# IPMC_V71V01.net
KiCad netlist of a schematic drawn in Altium Designer
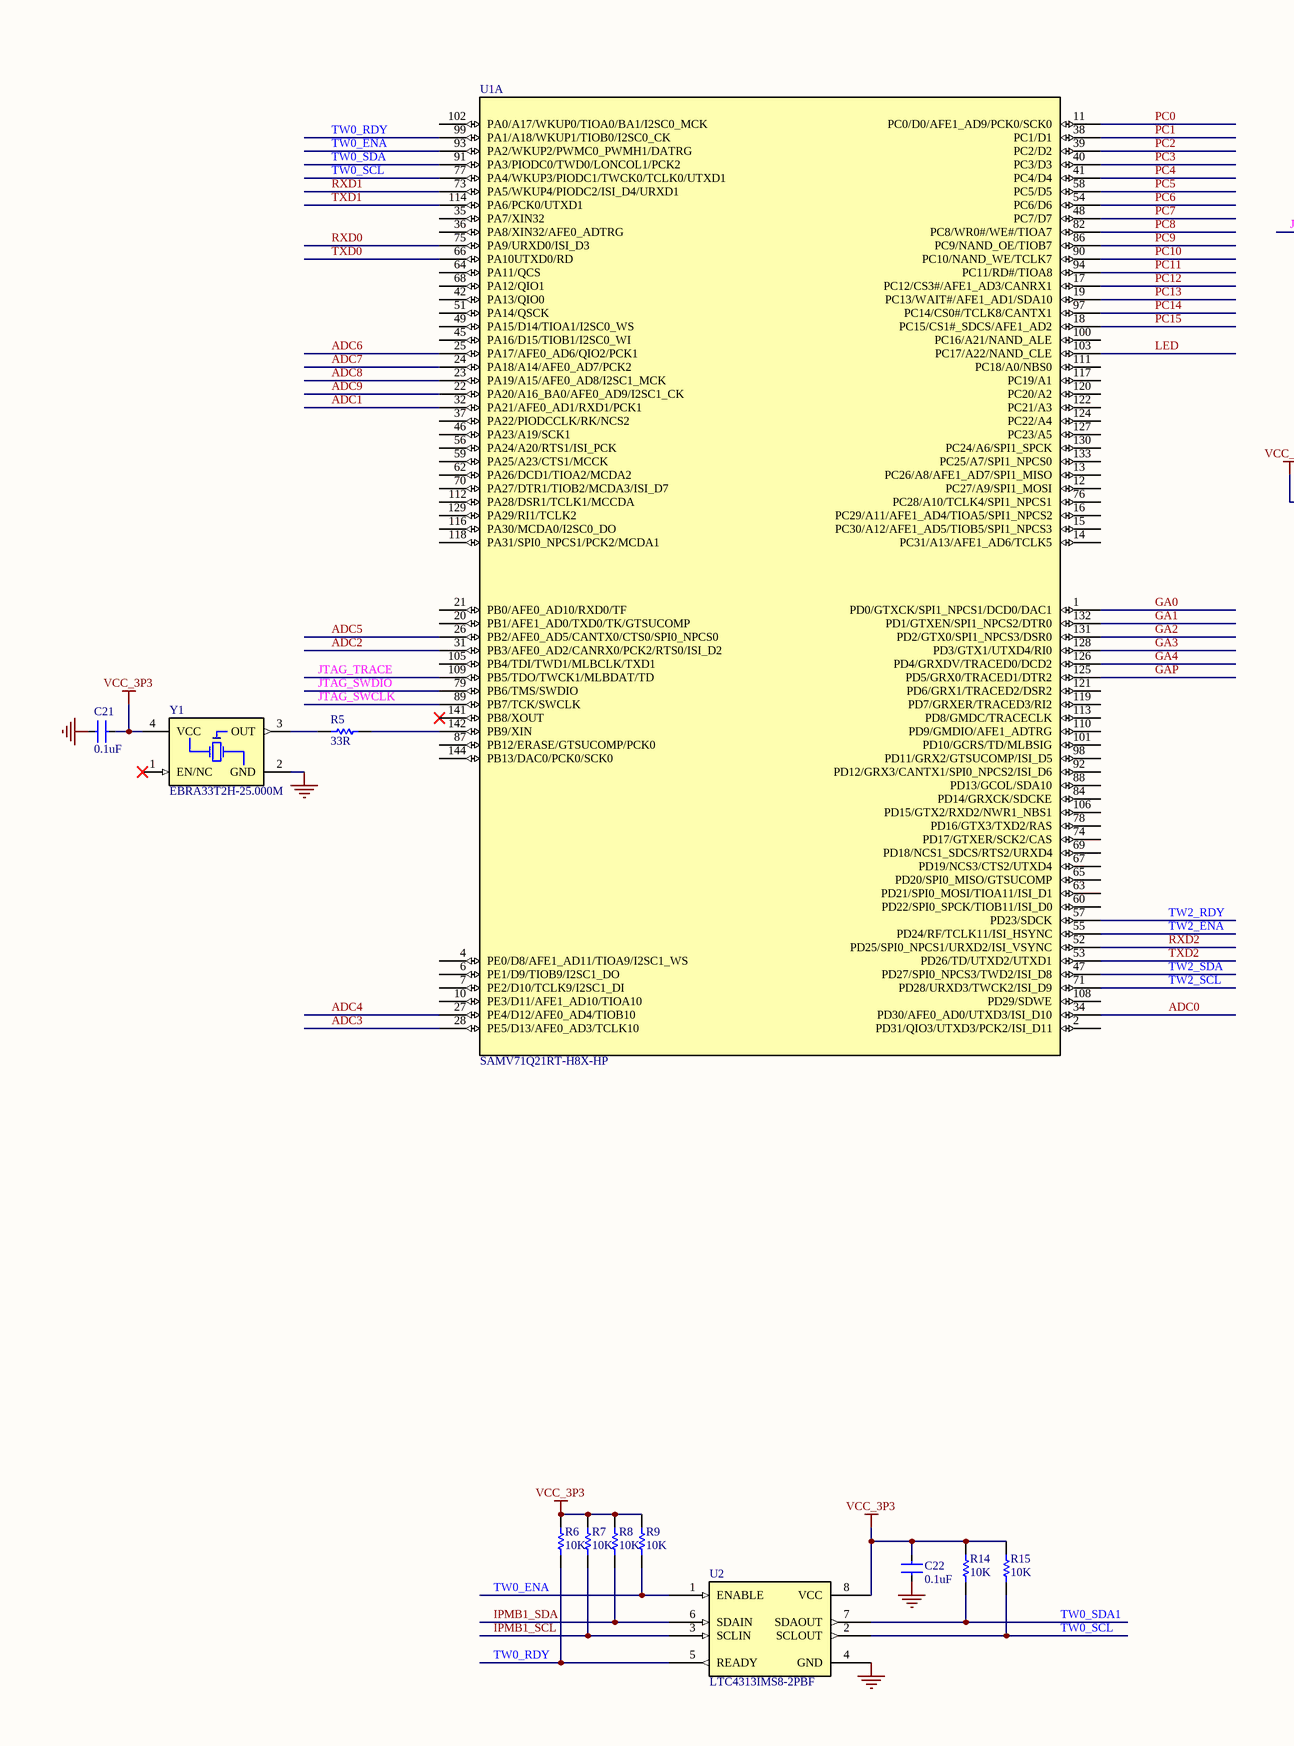
[diagram p0: IPMC_V71V01.SchDoc, left]
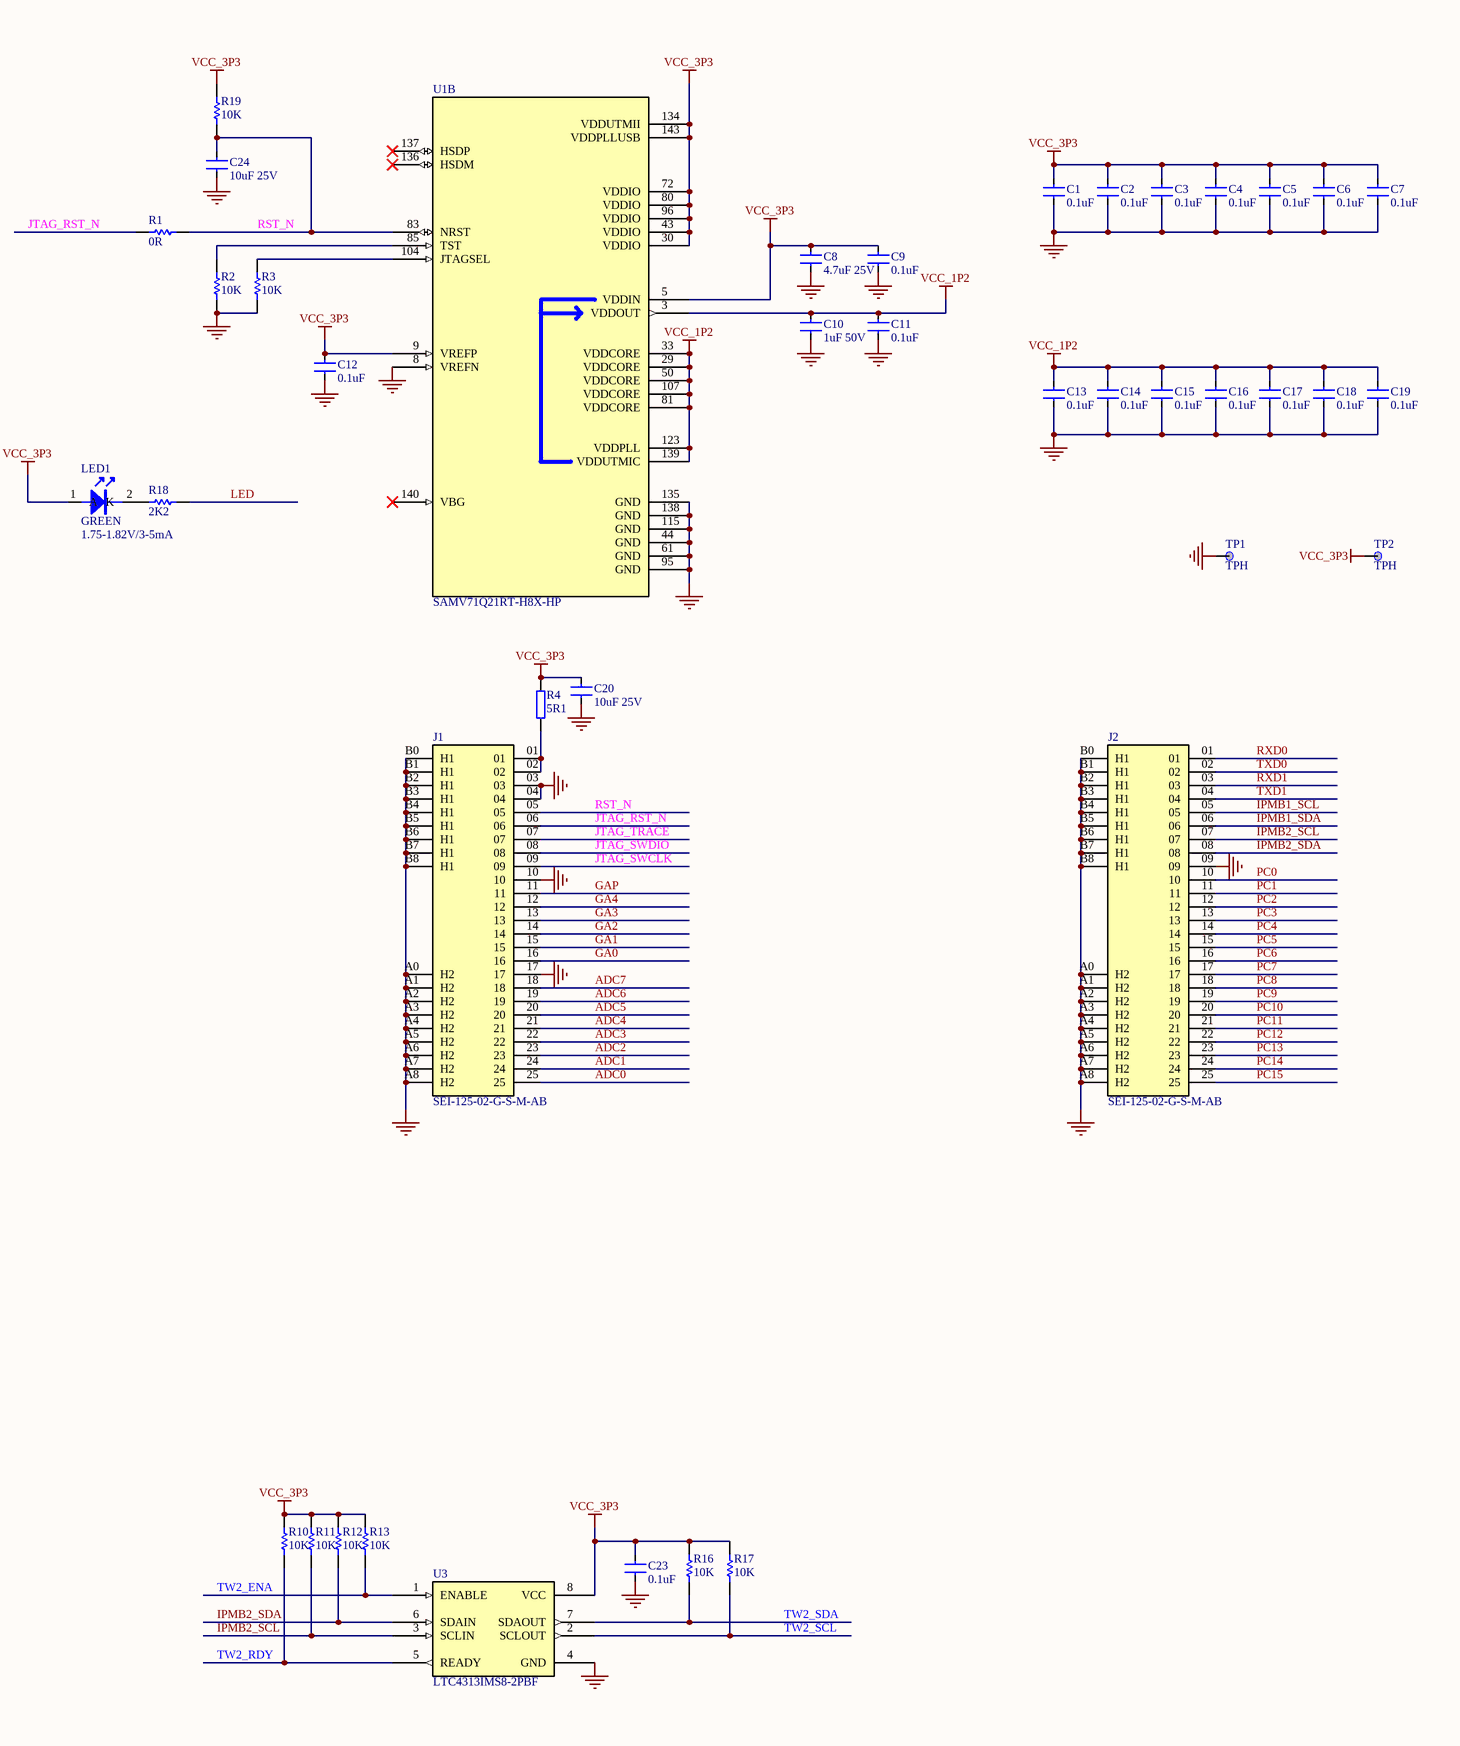
[diagram p1: IPMC_V71V01.SchDoc, right]

(export (version "E")
  (design (tool "Eeschema 10.0.6"))
  (components
    (comp (ref "C1")
      (value "0.1uF")
      (footprint "0603C")
      (description "X8L AEC-Q200")
      (fields (field (name "MANUFACTURER") "muRata") (field (name "PARTNUMBER") "GCJ188L8EL104KA07"))
      (libsource (lib "AD20_RCX") (part "CAP-0.1u-100v-0603"))
    )
    (comp (ref "C2")
      (value "0.1uF")
      (footprint "0603C")
      (description "X8L AEC-Q200")
      (fields (field (name "MANUFACTURER") "muRata") (field (name "PARTNUMBER") "GCJ188L8EL104KA07"))
      (libsource (lib "AD20_RCX") (part "CAP-0.1u-100v-0603"))
    )
    (comp (ref "C3")
      (value "0.1uF")
      (footprint "0603C")
      (description "X8L AEC-Q200")
      (fields (field (name "MANUFACTURER") "muRata") (field (name "PARTNUMBER") "GCJ188L8EL104KA07"))
      (libsource (lib "AD20_RCX") (part "CAP-0.1u-100v-0603"))
    )
    (comp (ref "C4")
      (value "0.1uF")
      (footprint "0603C")
      (description "X8L AEC-Q200")
      (fields (field (name "MANUFACTURER") "muRata") (field (name "PARTNUMBER") "GCJ188L8EL104KA07"))
      (libsource (lib "AD20_RCX") (part "CAP-0.1u-100v-0603"))
    )
    (comp (ref "C5")
      (value "0.1uF")
      (footprint "0603C")
      (description "X8L AEC-Q200")
      (fields (field (name "MANUFACTURER") "muRata") (field (name "PARTNUMBER") "GCJ188L8EL104KA07"))
      (libsource (lib "AD20_RCX") (part "CAP-0.1u-100v-0603"))
    )
    (comp (ref "C6")
      (value "0.1uF")
      (footprint "0603C")
      (description "X8L AEC-Q200")
      (fields (field (name "MANUFACTURER") "muRata") (field (name "PARTNUMBER") "GCJ188L8EL104KA07"))
      (libsource (lib "AD20_RCX") (part "CAP-0.1u-100v-0603"))
    )
    (comp (ref "C7")
      (value "0.1uF")
      (footprint "0603C")
      (description "X8L AEC-Q200")
      (fields (field (name "MANUFACTURER") "muRata") (field (name "PARTNUMBER") "GCJ188L8EL104KA07"))
      (libsource (lib "AD20_RCX") (part "CAP-0.1u-100v-0603"))
    )
    (comp (ref "C8")
      (value "4.7uF 25V")
      (footprint "0603C")
      (description "X5R AEC-Q200")
      (fields (field (name "PARTNUMBER") "GRT188R61E475KE13") (field (name "MANUFACTURER") "muRata"))
      (libsource (lib "AD20_RCX") (part "CAP-4.7u-25v-0603"))
    )
    (comp (ref "C9")
      (value "0.1uF")
      (footprint "0603C")
      (description "X8L AEC-Q200")
      (fields (field (name "MANUFACTURER") "muRata") (field (name "PARTNUMBER") "GCJ188L8EL104KA07"))
      (libsource (lib "AD20_RCX") (part "CAP-0.1u-100v-0603"))
    )
    (comp (ref "C10")
      (value "1uF 50V")
      (footprint "0603C")
      (description "X5R AEC-Q200")
      (fields (field (name "PARTNUMBER") "GRT188R61H105KE13") (field (name "MANUFACTURER") "muRata"))
      (libsource (lib "AD20_RCX") (part "CAP-1u-50v-0603"))
    )
    (comp (ref "C11")
      (value "0.1uF")
      (footprint "0603C")
      (description "X8L AEC-Q200")
      (fields (field (name "MANUFACTURER") "muRata") (field (name "PARTNUMBER") "GCJ188L8EL104KA07"))
      (libsource (lib "AD20_RCX") (part "CAP-0.1u-100v-0603"))
    )
    (comp (ref "C12")
      (value "0.1uF")
      (footprint "0603C")
      (description "X8L AEC-Q200")
      (fields (field (name "MANUFACTURER") "muRata") (field (name "PARTNUMBER") "GCJ188L8EL104KA07"))
      (libsource (lib "AD20_RCX") (part "CAP-0.1u-100v-0603"))
    )
    (comp (ref "C13")
      (value "0.1uF")
      (footprint "0603C")
      (description "X8L AEC-Q200")
      (fields (field (name "MANUFACTURER") "muRata") (field (name "PARTNUMBER") "GCJ188L8EL104KA07"))
      (libsource (lib "AD20_RCX") (part "CAP-0.1u-100v-0603"))
    )
    (comp (ref "C14")
      (value "0.1uF")
      (footprint "0603C")
      (description "X8L AEC-Q200")
      (fields (field (name "MANUFACTURER") "muRata") (field (name "PARTNUMBER") "GCJ188L8EL104KA07"))
      (libsource (lib "AD20_RCX") (part "CAP-0.1u-100v-0603"))
    )
    (comp (ref "C15")
      (value "0.1uF")
      (footprint "0603C")
      (description "X8L AEC-Q200")
      (fields (field (name "MANUFACTURER") "muRata") (field (name "PARTNUMBER") "GCJ188L8EL104KA07"))
      (libsource (lib "AD20_RCX") (part "CAP-0.1u-100v-0603"))
    )
    (comp (ref "C16")
      (value "0.1uF")
      (footprint "0603C")
      (description "X8L AEC-Q200")
      (fields (field (name "MANUFACTURER") "muRata") (field (name "PARTNUMBER") "GCJ188L8EL104KA07"))
      (libsource (lib "AD20_RCX") (part "CAP-0.1u-100v-0603"))
    )
    (comp (ref "C17")
      (value "0.1uF")
      (footprint "0603C")
      (description "X8L AEC-Q200")
      (fields (field (name "MANUFACTURER") "muRata") (field (name "PARTNUMBER") "GCJ188L8EL104KA07"))
      (libsource (lib "AD20_RCX") (part "CAP-0.1u-100v-0603"))
    )
    (comp (ref "C18")
      (value "0.1uF")
      (footprint "0603C")
      (description "X8L AEC-Q200")
      (fields (field (name "MANUFACTURER") "muRata") (field (name "PARTNUMBER") "GCJ188L8EL104KA07"))
      (libsource (lib "AD20_RCX") (part "CAP-0.1u-100v-0603"))
    )
    (comp (ref "C19")
      (value "0.1uF")
      (footprint "0603C")
      (description "X8L AEC-Q200")
      (fields (field (name "MANUFACTURER") "muRata") (field (name "PARTNUMBER") "GCJ188L8EL104KA07"))
      (libsource (lib "AD20_RCX") (part "CAP-0.1u-100v-0603"))
    )
    (comp (ref "C20")
      (value "10uF 25V")
      (footprint "0603C")
      (description "X5R AEC-Q200")
      (fields (field (name "PARTNUMBER") "GRT188R61E106ME13") (field (name "MANUFACTURER") "muRata"))
      (libsource (lib "AD20_RCX") (part "CAP-10u-25v-0603"))
    )
    (comp (ref "C21")
      (value "0.1uF")
      (footprint "0603C")
      (description "X7R AEC-Q200")
      (fields (field (name "PARTNUMBER") "GCJ188R71H104KA12") (field (name "MANUFACTURER") "muRata"))
      (libsource (lib "AD") (part "CAP-0.1u-50v-0603"))
    )
    (comp (ref "C22")
      (value "0.1uF")
      (footprint "0603C")
      (description "X7R AEC-Q200")
      (fields (field (name "PARTNUMBER") "GCJ188R71H104KA12") (field (name "MANUFACTURER") "muRata"))
      (libsource (lib "AD") (part "CAP-0.1u-50v-0603"))
    )
    (comp (ref "C23")
      (value "0.1uF")
      (footprint "0603C")
      (description "X7R AEC-Q200")
      (fields (field (name "PARTNUMBER") "GCJ188R71H104KA12") (field (name "MANUFACTURER") "muRata"))
      (libsource (lib "AD") (part "CAP-0.1u-50v-0603"))
    )
    (comp (ref "C24")
      (value "10uF 25V")
      (footprint "0603C")
      (description "X5R AEC-Q200")
      (fields (field (name "PARTNUMBER") "GRT188R61E106ME13") (field (name "MANUFACTURER") "muRata"))
      (libsource (lib "AD20_RCX") (part "CAP-10u-25v-0603"))
    )
    (comp (ref "J1")
      (value "SEI-125-02-G-S-M-AB")
      (footprint "SAMTEC_SEI-125-02-G-S-M-AB_IPMC")
      (description "25 Position Spring Compression Contact, Non-Gendered Connector Surface Mount")
      (fields (field (name "MF") "Samtec") (field (name "MP") "SEI-125-02-G-S-E-AB"))
      (libsource (lib "ChMC_V71V01_PCB_Project") (part "SEI-125-02-G-S-E-AB"))
    )
    (comp (ref "J2")
      (value "SEI-125-02-G-S-M-AB")
      (footprint "SAMTEC_SEI-125-02-G-S-M-AB_IPMC")
      (description "25 Position Spring Compression Contact, Non-Gendered Connector Surface Mount")
      (fields (field (name "MF") "Samtec") (field (name "MP") "SEI-125-02-G-S-E-AB"))
      (libsource (lib "ChMC_V71V01_PCB_Project") (part "SEI-125-02-G-S-E-AB"))
    )
    (comp (ref "LED1")
      (value "GREEN")
      (footprint "0603LED")
      (description "1.75-1.82V/3-5mA")
      (fields (field (name "PARAMETER 1") "1.75-1.82V/3-5mA"))
      (libsource (lib "AD20_RCX") (part "D-LED0603-GREEN"))
    )
    (comp (ref "R1")
      (value "0R")
      (footprint "0603R")
      (description "1%/0603")
      (fields (field (name "PARTNUMBER") "AC0603FR-070RL") (field (name "MANUFACTURER") "YAGEO"))
      (libsource (lib "AD20_RCX") (part "Res1-0R"))
    )
    (comp (ref "R2")
      (value "10K")
      (footprint "0603R")
      (description "1%/0603")
      (fields (field (name "PARTNUMBER") "AC0603FR-0710KL") (field (name "MANUFACTURER") "YAGEO"))
      (libsource (lib "AD20_RCX") (part "Res1-10K"))
    )
    (comp (ref "R3")
      (value "10K")
      (footprint "0603R")
      (description "1%/0603")
      (fields (field (name "PARTNUMBER") "AC0603FR-0710KL") (field (name "MANUFACTURER") "YAGEO"))
      (libsource (lib "AD20_RCX") (part "Res1-10K"))
    )
    (comp (ref "R4")
      (value "5R1")
      (footprint "0805R")
      (description "1%/0805")
      (fields (field (name "PARTNUMBER") "AC0805FR-075R1L") (field (name "MANUFACTURER") "YAGEO"))
      (libsource (lib "AD20_RCX") (part "Res2-5R1-0805"))
    )
    (comp (ref "R5")
      (value "33R")
      (footprint "0603R")
      (description "1%/0603")
      (fields (field (name "PARTNUMBER") "AC0603FR-0733RL") (field (name "MANUFACTURER") "YAGEO"))
      (libsource (lib "AD20_RCX") (part "Res1-33R"))
    )
    (comp (ref "R6")
      (value "10K")
      (footprint "0603R")
      (description "1%/0603")
      (fields (field (name "PARTNUMBER") "AC0603FR-0710KL") (field (name "MANUFACTURER") "YAGEO"))
      (libsource (lib "AD20_RCX") (part "Res1-10K"))
    )
    (comp (ref "R7")
      (value "10K")
      (footprint "0603R")
      (description "1%/0603")
      (fields (field (name "PARTNUMBER") "AC0603FR-0710KL") (field (name "MANUFACTURER") "YAGEO"))
      (libsource (lib "AD20_RCX") (part "Res1-10K"))
    )
    (comp (ref "R8")
      (value "10K")
      (footprint "0603R")
      (description "1%/0603")
      (fields (field (name "PARTNUMBER") "AC0603FR-0710KL") (field (name "MANUFACTURER") "YAGEO"))
      (libsource (lib "AD20_RCX") (part "Res1-10K"))
    )
    (comp (ref "R9")
      (value "10K")
      (footprint "0603R")
      (description "1%/0603")
      (fields (field (name "PARTNUMBER") "AC0603FR-0710KL") (field (name "MANUFACTURER") "YAGEO"))
      (libsource (lib "AD20_RCX") (part "Res1-10K"))
    )
    (comp (ref "R10")
      (value "10K")
      (footprint "0603R")
      (description "1%/0603")
      (fields (field (name "PARTNUMBER") "AC0603FR-0710KL") (field (name "MANUFACTURER") "YAGEO"))
      (libsource (lib "AD20_RCX") (part "Res1-10K"))
    )
    (comp (ref "R11")
      (value "10K")
      (footprint "0603R")
      (description "1%/0603")
      (fields (field (name "PARTNUMBER") "AC0603FR-0710KL") (field (name "MANUFACTURER") "YAGEO"))
      (libsource (lib "AD20_RCX") (part "Res1-10K"))
    )
    (comp (ref "R12")
      (value "10K")
      (footprint "0603R")
      (description "1%/0603")
      (fields (field (name "PARTNUMBER") "AC0603FR-0710KL") (field (name "MANUFACTURER") "YAGEO"))
      (libsource (lib "AD20_RCX") (part "Res1-10K"))
    )
    (comp (ref "R13")
      (value "10K")
      (footprint "0603R")
      (description "1%/0603")
      (fields (field (name "PARTNUMBER") "AC0603FR-0710KL") (field (name "MANUFACTURER") "YAGEO"))
      (libsource (lib "AD20_RCX") (part "Res1-10K"))
    )
    (comp (ref "R14")
      (value "10K")
      (footprint "0603R")
      (description "1%/0603")
      (fields (field (name "PARTNUMBER") "AC0603FR-0710KL") (field (name "MANUFACTURER") "YAGEO"))
      (libsource (lib "IPMCv01_PCB_Project") (part "Res1-10K"))
    )
    (comp (ref "R15")
      (value "10K")
      (footprint "0603R")
      (description "1%/0603")
      (fields (field (name "PARTNUMBER") "AC0603FR-0710KL") (field (name "MANUFACTURER") "YAGEO"))
      (libsource (lib "IPMCv01_PCB_Project") (part "Res1-10K"))
    )
    (comp (ref "R16")
      (value "10K")
      (footprint "0603R")
      (description "1%/0603")
      (fields (field (name "PARTNUMBER") "AC0603FR-0710KL") (field (name "MANUFACTURER") "YAGEO"))
      (libsource (lib "IPMCv01_PCB_Project") (part "Res1-10K"))
    )
    (comp (ref "R17")
      (value "10K")
      (footprint "0603R")
      (description "1%/0603")
      (fields (field (name "PARTNUMBER") "AC0603FR-0710KL") (field (name "MANUFACTURER") "YAGEO"))
      (libsource (lib "IPMCv01_PCB_Project") (part "Res1-10K"))
    )
    (comp (ref "R18")
      (value "2K2")
      (footprint "0603R")
      (description "1%/0603")
      (fields (field (name "PARTNUMBER") "AC0603FR-072K2L") (field (name "MANUFACTURER") "YAGEO"))
      (libsource (lib "AD20_RCX") (part "Res1-2K2"))
    )
    (comp (ref "R19")
      (value "10K")
      (footprint "0603R")
      (description "1%/0603")
      (fields (field (name "PARTNUMBER") "AC0603FR-0710KL") (field (name "MANUFACTURER") "YAGEO"))
      (libsource (lib "AD20_RCX") (part "Res1-10K"))
    )
    (comp (ref "TP1") (value "TPH") (footprint "TP") (libsource (lib "AD20_CON") (part "TPH")))
    (comp (ref "TP2") (value "TPH") (footprint "TP") (libsource (lib "AD20_CON") (part "TPH")))
    (comp (ref "U1")
      (value "SAMV71Q21RT-H8X-HP")
      (footprint "LQFP144_2SB_MCH")
      (description "No Description Available")
      (libsource (lib "AD20_IC") (part "SAMV71Q21RT-H8X-HP"))
    )
    (comp (ref "U2")
      (value "LTC4313IMS8-2PBF")
      (footprint "MSOP-8_MS_LIT")
      (description "No Description Available")
      (libsource (lib "AD20_IC") (part "LTC4313IMS8-1PBF"))
    )
    (comp (ref "U3")
      (value "LTC4313IMS8-2PBF")
      (footprint "MSOP-8_MS_LIT")
      (description "No Description Available")
      (libsource (lib "AD20_IC") (part "LTC4313IMS8-1PBF"))
    )
    (comp (ref "Y1")
      (value "EBRA33T2H-25.000M")
      (footprint "50.000M 3P3 50PPM 10PF 3.2*5.0MM")
      (description "SPXO AEC-Q200")
      (fields (field (name "MANUFACTURER") "Ecliptec") (field (name "PARTNUMBER") "EBRA23T1H-50.000M"))
      (libsource (lib "AD20_RCX") (part "XTAL3_50M_SPXO_3.2_5.0"))
    )
  )
  (nets
    (net (code "1") (name "/ADC0") (class "Default")
      (node (ref "J1") (pin "25") (pinfunction "25_25") (pintype "passive"))
      (node (ref "U1") (pin "34") (pinfunction "PD30/UTXD3/ISI_D10_34") (pintype "bidirectional"))
    )
    (net (code "2") (name "/ADC1") (class "Default")
      (node (ref "J1") (pin "24") (pinfunction "24_24") (pintype "passive"))
      (node (ref "U1") (pin "32") (pinfunction "PA21/AFE0_AD1/RXD1/PCK1_32") (pintype "bidirectional"))
    )
    (net (code "3") (name "/ADC2") (class "Default")
      (node (ref "J1") (pin "23") (pinfunction "23_23") (pintype "passive"))
      (node (ref "U1") (pin "31") (pinfunction "PB3/AFE0_AD2/CANRX0/PCK2/RTS0/ISI_D2_31") (pintype "bidirectional"))
    )
    (net (code "4") (name "/ADC3") (class "Default")
      (node (ref "J1") (pin "22") (pinfunction "22_22") (pintype "passive"))
      (node (ref "U1") (pin "28") (pinfunction "PE5/D13/AFE0_AD3/TCLK10_28") (pintype "bidirectional"))
    )
    (net (code "5") (name "/ADC4") (class "Default")
      (node (ref "J1") (pin "21") (pinfunction "21_21") (pintype "passive"))
      (node (ref "U1") (pin "27") (pinfunction "PE4/D12/AFE0_AD4/TIOB10_27") (pintype "bidirectional"))
    )
    (net (code "6") (name "/ADC5") (class "Default")
      (node (ref "J1") (pin "20") (pinfunction "20_20") (pintype "passive"))
      (node (ref "U1") (pin "26") (pinfunction "PB2/AFE0_AD5/CANTX0/CTS0/SPI0_NPCS0_26") (pintype "bidirectional"))
    )
    (net (code "7") (name "/ADC6") (class "Default")
      (node (ref "J1") (pin "19") (pinfunction "19_19") (pintype "passive"))
      (node (ref "U1") (pin "25") (pinfunction "PA17/AFE0_AD6/QIO2/PCK1_25") (pintype "bidirectional"))
    )
    (net (code "8") (name "/ADC7") (class "Default")
      (node (ref "J1") (pin "18") (pinfunction "18_18") (pintype "passive"))
      (node (ref "U1") (pin "24") (pinfunction "PA18/A14/AFE0_AD7/PCK2_24") (pintype "bidirectional"))
    )
    (net (code "9") (name "/ADC8") (class "Default")
      (node (ref "U1") (pin "23") (pinfunction "PA19/A15/AFE0_AD8/I2SC1_MCK_23") (pintype "bidirectional"))
    )
    (net (code "10") (name "/ADC9") (class "Default")
      (node (ref "U1") (pin "22") (pinfunction "PA20/A16_BA0/AFE0_AD9/I2SC1_CK_22") (pintype "bidirectional"))
    )
    (net (code "11") (name "/GA0") (class "Default")
      (node (ref "J1") (pin "16") (pinfunction "16_16") (pintype "passive"))
      (node (ref "U1") (pin "1") (pinfunction "PD0/GTXCK/SPI1_NPCS1/DCD0/DAC1_1") (pintype "bidirectional"))
    )
    (net (code "12") (name "/GA1") (class "Default")
      (node (ref "J1") (pin "15") (pinfunction "15_15") (pintype "passive"))
      (node (ref "U1") (pin "132") (pinfunction "PD1/GTXEN/SPI1_NPCS2/DTR0_132") (pintype "bidirectional"))
    )
    (net (code "13") (name "/GA2") (class "Default")
      (node (ref "J1") (pin "14") (pinfunction "14_14") (pintype "passive"))
      (node (ref "U1") (pin "131") (pinfunction "PD2/GTX0/SPI1_NPCS3/DSR0_131") (pintype "bidirectional"))
    )
    (net (code "14") (name "/GA3") (class "Default")
      (node (ref "J1") (pin "13") (pinfunction "13_13") (pintype "passive"))
      (node (ref "U1") (pin "128") (pinfunction "PD3/GTX1/UTXD4/RI0_128") (pintype "bidirectional"))
    )
    (net (code "15") (name "/GA4") (class "Default")
      (node (ref "J1") (pin "12") (pinfunction "12_12") (pintype "passive"))
      (node (ref "U1") (pin "126") (pinfunction "PD4/GRXDV/TRACED0/DCD2_126") (pintype "bidirectional"))
    )
    (net (code "16") (name "/GAP") (class "Default")
      (node (ref "J1") (pin "11") (pinfunction "11_11") (pintype "passive"))
      (node (ref "U1") (pin "125") (pinfunction "PD5/GRX0/TRACED1/DTR2_125") (pintype "bidirectional"))
    )
    (net (code "17") (name "/IPMB1_SCL") (class "Default")
      (node (ref "J2") (pin "05") (pinfunction "05_05") (pintype "passive"))
      (node (ref "R7") (pin "1") (pinfunction "1_1") (pintype "passive"))
      (node (ref "U2") (pin "3") (pinfunction "SCLIN_3") (pintype "input"))
    )
    (net (code "18") (name "/IPMB1_SDA") (class "Default")
      (node (ref "J2") (pin "06") (pinfunction "06_06") (pintype "passive"))
      (node (ref "R8") (pin "1") (pinfunction "1_1") (pintype "passive"))
      (node (ref "U2") (pin "6") (pinfunction "SDAIN_6") (pintype "input"))
    )
    (net (code "19") (name "/IPMB2_SCL") (class "Default")
      (node (ref "J2") (pin "07") (pinfunction "07_07") (pintype "passive"))
      (node (ref "R11") (pin "1") (pinfunction "1_1") (pintype "passive"))
      (node (ref "U3") (pin "3") (pinfunction "SCLIN_3") (pintype "input"))
    )
    (net (code "20") (name "/IPMB2_SDA") (class "Default")
      (node (ref "J2") (pin "08") (pinfunction "08_08") (pintype "passive"))
      (node (ref "R12") (pin "1") (pinfunction "1_1") (pintype "passive"))
      (node (ref "U3") (pin "6") (pinfunction "SDAIN_6") (pintype "input"))
    )
    (net (code "21") (name "/JTAG_RST_N") (class "Default")
      (node (ref "J1") (pin "06") (pinfunction "06_06") (pintype "passive"))
      (node (ref "R1") (pin "1") (pinfunction "1_1") (pintype "passive"))
    )
    (net (code "22") (name "/JTAG_SWCLK") (class "Default")
      (node (ref "J1") (pin "09") (pinfunction "09_09") (pintype "passive"))
      (node (ref "U1") (pin "89") (pinfunction "PB7/TCK/SWCLK_89") (pintype "bidirectional"))
    )
    (net (code "23") (name "/JTAG_SWDIO") (class "Default")
      (node (ref "J1") (pin "08") (pinfunction "08_08") (pintype "passive"))
      (node (ref "U1") (pin "79") (pinfunction "PB6/TMS/SWDIO_79") (pintype "bidirectional"))
    )
    (net (code "24") (name "/JTAG_TRACE") (class "Default")
      (node (ref "J1") (pin "07") (pinfunction "07_07") (pintype "passive"))
      (node (ref "U1") (pin "109") (pinfunction "PB5/TDO/TWCK1/MLBDAT/TD_109") (pintype "bidirectional"))
    )
    (net (code "25") (name "/LED") (class "Default")
      (node (ref "R18") (pin "2") (pinfunction "2_2") (pintype "passive"))
      (node (ref "U1") (pin "103") (pinfunction "PC17/A22/NAND_CLE_103") (pintype "bidirectional"))
    )
    (net (code "26") (name "/PC0") (class "Default")
      (node (ref "J2") (pin "10") (pinfunction "10_10") (pintype "passive"))
      (node (ref "U1") (pin "11") (pinfunction "PC0/D0/AFE1_AD9/PCK0/SCK0_11") (pintype "bidirectional"))
    )
    (net (code "27") (name "/PC1") (class "Default")
      (node (ref "J2") (pin "11") (pinfunction "11_11") (pintype "passive"))
      (node (ref "U1") (pin "38") (pinfunction "PC1/D1_38") (pintype "bidirectional"))
    )
    (net (code "28") (name "/PC2") (class "Default")
      (node (ref "J2") (pin "12") (pinfunction "12_12") (pintype "passive"))
      (node (ref "U1") (pin "39") (pinfunction "PC2/D2_39") (pintype "bidirectional"))
    )
    (net (code "29") (name "/PC3") (class "Default")
      (node (ref "J2") (pin "13") (pinfunction "13_13") (pintype "passive"))
      (node (ref "U1") (pin "40") (pinfunction "PC3/D3_40") (pintype "bidirectional"))
    )
    (net (code "30") (name "/PC4") (class "Default")
      (node (ref "J2") (pin "14") (pinfunction "14_14") (pintype "passive"))
      (node (ref "U1") (pin "41") (pinfunction "PC4/D4_41") (pintype "bidirectional"))
    )
    (net (code "31") (name "/PC5") (class "Default")
      (node (ref "J2") (pin "15") (pinfunction "15_15") (pintype "passive"))
      (node (ref "U1") (pin "58") (pinfunction "PC5/D5_58") (pintype "bidirectional"))
    )
    (net (code "32") (name "/PC6") (class "Default")
      (node (ref "J2") (pin "16") (pinfunction "16_16") (pintype "passive"))
      (node (ref "U1") (pin "54") (pinfunction "PC6/D6_54") (pintype "bidirectional"))
    )
    (net (code "33") (name "/PC7") (class "Default")
      (node (ref "J2") (pin "17") (pinfunction "17_17") (pintype "passive"))
      (node (ref "U1") (pin "48") (pinfunction "PC7/D7_48") (pintype "bidirectional"))
    )
    (net (code "34") (name "/PC8") (class "Default")
      (node (ref "J2") (pin "18") (pinfunction "18_18") (pintype "passive"))
      (node (ref "U1") (pin "82") (pinfunction "PC8/WR0#/WE#/TIOA7_82") (pintype "bidirectional"))
    )
    (net (code "35") (name "/PC9") (class "Default")
      (node (ref "J2") (pin "19") (pinfunction "19_19") (pintype "passive"))
      (node (ref "U1") (pin "86") (pinfunction "PC9/NAND_OE/TIOB7_86") (pintype "bidirectional"))
    )
    (net (code "36") (name "/PC10") (class "Default")
      (node (ref "J2") (pin "20") (pinfunction "20_20") (pintype "passive"))
      (node (ref "U1") (pin "90") (pinfunction "PC10/NAND_WE/TCLK7_90") (pintype "bidirectional"))
    )
    (net (code "37") (name "/PC11") (class "Default")
      (node (ref "J2") (pin "21") (pinfunction "21_21") (pintype "passive"))
      (node (ref "U1") (pin "94") (pinfunction "PC11/RD#/TIOA8_94") (pintype "bidirectional"))
    )
    (net (code "38") (name "/PC12") (class "Default")
      (node (ref "J2") (pin "22") (pinfunction "22_22") (pintype "passive"))
      (node (ref "U1") (pin "17") (pinfunction "PC12/CS3#/AFE1_AD3/CANRX1_17") (pintype "bidirectional"))
    )
    (net (code "39") (name "/PC13") (class "Default")
      (node (ref "J2") (pin "23") (pinfunction "23_23") (pintype "passive"))
      (node (ref "U1") (pin "19") (pinfunction "PC13/WAIT#/AFE1_AD1/SDA10_19") (pintype "bidirectional"))
    )
    (net (code "40") (name "/PC14") (class "Default")
      (node (ref "J2") (pin "24") (pinfunction "24_24") (pintype "passive"))
      (node (ref "U1") (pin "97") (pinfunction "PC14/CS0#/TCLK8/CANTX1_97") (pintype "bidirectional"))
    )
    (net (code "41") (name "/PC15") (class "Default")
      (node (ref "J2") (pin "25") (pinfunction "25_25") (pintype "passive"))
      (node (ref "U1") (pin "18") (pinfunction "PC15/CS1#_SDCS/AFE1_AD2_18") (pintype "bidirectional"))
    )
    (net (code "42") (name "/RST_N") (class "Default")
      (node (ref "C24") (pin "2") (pinfunction "2_2") (pintype "passive"))
      (node (ref "J1") (pin "05") (pinfunction "05_05") (pintype "passive"))
      (node (ref "R1") (pin "2") (pinfunction "2_2") (pintype "passive"))
      (node (ref "R19") (pin "1") (pinfunction "1_1") (pintype "passive"))
      (node (ref "U1") (pin "83") (pinfunction "NRST_83") (pintype "bidirectional"))
    )
    (net (code "43") (name "/RXD0") (class "Default")
      (node (ref "J2") (pin "01") (pinfunction "01_01") (pintype "passive"))
      (node (ref "U1") (pin "75") (pinfunction "PA9/URXD0/ISI_D3_75") (pintype "bidirectional"))
    )
    (net (code "44") (name "/RXD1") (class "Default")
      (node (ref "J2") (pin "03") (pinfunction "03_03") (pintype "passive"))
      (node (ref "U1") (pin "73") (pinfunction "PA5/WKUP4/PIODC2/ISI_D4/URXD1_73") (pintype "bidirectional"))
    )
    (net (code "45") (name "/RXD2") (class "Default")
      (node (ref "U1") (pin "52") (pinfunction "PD25/SPI0_NPCS1/URXD2/ISI_VSYNC_52") (pintype "bidirectional"))
    )
    (net (code "46") (name "/TW0_ENA") (class "Default")
      (node (ref "R9") (pin "1") (pinfunction "1_1") (pintype "passive"))
      (node (ref "U1") (pin "93") (pinfunction "PA2/WKUP2/PWMC0_PWMH1/DATRG_93") (pintype "bidirectional"))
      (node (ref "U2") (pin "1") (pinfunction "ENABLE_1") (pintype "input"))
    )
    (net (code "47") (name "/TW0_RDY") (class "Default")
      (node (ref "R6") (pin "1") (pinfunction "1_1") (pintype "passive"))
      (node (ref "U1") (pin "99") (pinfunction "PA1/A18/WKUP1/TIOB0/I2SC0_CK_99") (pintype "bidirectional"))
      (node (ref "U2") (pin "5") (pinfunction "READY_5") (pintype "output"))
    )
    (net (code "48") (name "/TW0_SCL") (class "Default")
      (node (ref "R15") (pin "1") (pinfunction "1_1") (pintype "passive"))
      (node (ref "U1") (pin "77") (pinfunction "PA4/WKUP3/PIODC1/TWCK0/TCLK0/UTXD1_77") (pintype "bidirectional"))
      (node (ref "U2") (pin "2") (pinfunction "SCLOUT_2") (pintype "output"))
    )
    (net (code "49") (name "/TW0_SDA") (class "Default")
      (node (ref "U1") (pin "91") (pinfunction "PA3/PIODC0/TWD0/LONCOL1/PCK2_91") (pintype "bidirectional"))
    )
    (net (code "50") (name "/TW0_SDA1") (class "Default")
      (node (ref "R14") (pin "1") (pinfunction "1_1") (pintype "passive"))
      (node (ref "U2") (pin "7") (pinfunction "SDAOUT_7") (pintype "output"))
    )
    (net (code "51") (name "/TW2_ENA") (class "Default")
      (node (ref "R13") (pin "1") (pinfunction "1_1") (pintype "passive"))
      (node (ref "U1") (pin "55") (pinfunction "PD24/RF/TCLK11/ISI_HSYNC_55") (pintype "bidirectional"))
      (node (ref "U3") (pin "1") (pinfunction "ENABLE_1") (pintype "input"))
    )
    (net (code "52") (name "/TW2_RDY") (class "Default")
      (node (ref "R10") (pin "1") (pinfunction "1_1") (pintype "passive"))
      (node (ref "U1") (pin "57") (pinfunction "PD23/SDCK_57") (pintype "bidirectional"))
      (node (ref "U3") (pin "5") (pinfunction "READY_5") (pintype "output"))
    )
    (net (code "53") (name "/TW2_SCL") (class "Default")
      (node (ref "R17") (pin "1") (pinfunction "1_1") (pintype "passive"))
      (node (ref "U1") (pin "71") (pinfunction "PD28/URXD3/TWCK2/ISI_D9_71") (pintype "bidirectional"))
      (node (ref "U3") (pin "2") (pinfunction "SCLOUT_2") (pintype "output"))
    )
    (net (code "54") (name "/TW2_SDA") (class "Default")
      (node (ref "R16") (pin "1") (pinfunction "1_1") (pintype "passive"))
      (node (ref "U1") (pin "47") (pinfunction "PD27/SPI0_NPCS3/TWD2/ISI_D8_47") (pintype "bidirectional"))
      (node (ref "U3") (pin "7") (pinfunction "SDAOUT_7") (pintype "output"))
    )
    (net (code "55") (name "/TXD0") (class "Default")
      (node (ref "J2") (pin "02") (pinfunction "02_02") (pintype "passive"))
      (node (ref "U1") (pin "66") (pinfunction "PA10UTXD0/RD_66") (pintype "bidirectional"))
    )
    (net (code "56") (name "/TXD1") (class "Default")
      (node (ref "J2") (pin "04") (pinfunction "04_04") (pintype "passive"))
      (node (ref "U1") (pin "114") (pinfunction "PA6/PCK0/UTXD1_114") (pintype "bidirectional"))
    )
    (net (code "57") (name "/TXD2") (class "Default")
      (node (ref "U1") (pin "53") (pinfunction "PD26/TD/UTXD2/UTXD1_53") (pintype "bidirectional"))
    )
    (net (code "58") (name "GND") (class "Default")
      (node (ref "C1") (pin "1") (pinfunction "1_1") (pintype "passive"))
      (node (ref "C10") (pin "1") (pinfunction "1_1") (pintype "passive"))
      (node (ref "C11") (pin "1") (pinfunction "1_1") (pintype "passive"))
      (node (ref "C12") (pin "1") (pinfunction "1_1") (pintype "passive"))
      (node (ref "C13") (pin "1") (pinfunction "1_1") (pintype "passive"))
      (node (ref "C14") (pin "1") (pinfunction "1_1") (pintype "passive"))
      (node (ref "C15") (pin "1") (pinfunction "1_1") (pintype "passive"))
      (node (ref "C16") (pin "1") (pinfunction "1_1") (pintype "passive"))
      (node (ref "C17") (pin "1") (pinfunction "1_1") (pintype "passive"))
      (node (ref "C18") (pin "1") (pinfunction "1_1") (pintype "passive"))
      (node (ref "C19") (pin "1") (pinfunction "1_1") (pintype "passive"))
      (node (ref "C2") (pin "1") (pinfunction "1_1") (pintype "passive"))
      (node (ref "C20") (pin "2") (pinfunction "2_2") (pintype "passive"))
      (node (ref "C21") (pin "1") (pinfunction "1_1") (pintype "passive"))
      (node (ref "C22") (pin "2") (pinfunction "2_2") (pintype "passive"))
      (node (ref "C23") (pin "2") (pinfunction "2_2") (pintype "passive"))
      (node (ref "C24") (pin "1") (pinfunction "1_1") (pintype "passive"))
      (node (ref "C3") (pin "1") (pinfunction "1_1") (pintype "passive"))
      (node (ref "C4") (pin "1") (pinfunction "1_1") (pintype "passive"))
      (node (ref "C5") (pin "1") (pinfunction "1_1") (pintype "passive"))
      (node (ref "C6") (pin "1") (pinfunction "1_1") (pintype "passive"))
      (node (ref "C7") (pin "1") (pinfunction "1_1") (pintype "passive"))
      (node (ref "C8") (pin "1") (pinfunction "1_1") (pintype "passive"))
      (node (ref "C9") (pin "1") (pinfunction "1_1") (pintype "passive"))
      (node (ref "J1") (pin "03") (pinfunction "03_03") (pintype "passive"))
      (node (ref "J1") (pin "04") (pinfunction "04_04") (pintype "passive"))
      (node (ref "J1") (pin "10") (pinfunction "10_10") (pintype "passive"))
      (node (ref "J1") (pin "17") (pinfunction "17_17") (pintype "passive"))
      (node (ref "J1") (pin "A0") (pinfunction "H2_A0") (pintype "passive"))
      (node (ref "J1") (pin "A1") (pinfunction "H2_A1") (pintype "passive"))
      (node (ref "J1") (pin "A2") (pinfunction "H2_A2") (pintype "passive"))
      (node (ref "J1") (pin "A3") (pinfunction "H2_A3") (pintype "passive"))
      (node (ref "J1") (pin "A4") (pinfunction "H2_A4") (pintype "passive"))
      (node (ref "J1") (pin "A5") (pinfunction "H2_A5") (pintype "passive"))
      (node (ref "J1") (pin "A6") (pinfunction "H2_A6") (pintype "passive"))
      (node (ref "J1") (pin "A7") (pinfunction "H2_A7") (pintype "passive"))
      (node (ref "J1") (pin "A8") (pinfunction "H2_A8") (pintype "passive"))
      (node (ref "J1") (pin "B0") (pinfunction "H1_B0") (pintype "passive"))
      (node (ref "J1") (pin "B1") (pinfunction "H1_B1") (pintype "passive"))
      (node (ref "J1") (pin "B2") (pinfunction "H1_B2") (pintype "passive"))
      (node (ref "J1") (pin "B3") (pinfunction "H1_B3") (pintype "passive"))
      (node (ref "J1") (pin "B4") (pinfunction "H1_B4") (pintype "passive"))
      (node (ref "J1") (pin "B5") (pinfunction "H1_B5") (pintype "passive"))
      (node (ref "J1") (pin "B6") (pinfunction "H1_B6") (pintype "passive"))
      (node (ref "J1") (pin "B7") (pinfunction "H1_B7") (pintype "passive"))
      (node (ref "J1") (pin "B8") (pinfunction "H1_B8") (pintype "passive"))
      (node (ref "J2") (pin "09") (pinfunction "09_09") (pintype "passive"))
      (node (ref "J2") (pin "A0") (pinfunction "H2_A0") (pintype "passive"))
      (node (ref "J2") (pin "A1") (pinfunction "H2_A1") (pintype "passive"))
      (node (ref "J2") (pin "A2") (pinfunction "H2_A2") (pintype "passive"))
      (node (ref "J2") (pin "A3") (pinfunction "H2_A3") (pintype "passive"))
      (node (ref "J2") (pin "A4") (pinfunction "H2_A4") (pintype "passive"))
      (node (ref "J2") (pin "A5") (pinfunction "H2_A5") (pintype "passive"))
      (node (ref "J2") (pin "A6") (pinfunction "H2_A6") (pintype "passive"))
      (node (ref "J2") (pin "A7") (pinfunction "H2_A7") (pintype "passive"))
      (node (ref "J2") (pin "A8") (pinfunction "H2_A8") (pintype "passive"))
      (node (ref "J2") (pin "B0") (pinfunction "H1_B0") (pintype "passive"))
      (node (ref "J2") (pin "B1") (pinfunction "H1_B1") (pintype "passive"))
      (node (ref "J2") (pin "B2") (pinfunction "H1_B2") (pintype "passive"))
      (node (ref "J2") (pin "B3") (pinfunction "H1_B3") (pintype "passive"))
      (node (ref "J2") (pin "B4") (pinfunction "H1_B4") (pintype "passive"))
      (node (ref "J2") (pin "B5") (pinfunction "H1_B5") (pintype "passive"))
      (node (ref "J2") (pin "B6") (pinfunction "H1_B6") (pintype "passive"))
      (node (ref "J2") (pin "B7") (pinfunction "H1_B7") (pintype "passive"))
      (node (ref "J2") (pin "B8") (pinfunction "H1_B8") (pintype "passive"))
      (node (ref "R2") (pin "1") (pinfunction "1_1") (pintype "passive"))
      (node (ref "R3") (pin "1") (pinfunction "1_1") (pintype "passive"))
      (node (ref "TP1") (pin "1") (pinfunction "1_1") (pintype "passive"))
      (node (ref "U1") (pin "115") (pinfunction "GND_115") (pintype "power_in"))
      (node (ref "U1") (pin "135") (pinfunction "GND_135") (pintype "power_in"))
      (node (ref "U1") (pin "138") (pinfunction "GND_138") (pintype "power_in"))
      (node (ref "U1") (pin "44") (pinfunction "GND_44") (pintype "power_in"))
      (node (ref "U1") (pin "61") (pinfunction "GND_61") (pintype "power_in"))
      (node (ref "U1") (pin "8") (pinfunction "VREFN_8") (pintype "input"))
      (node (ref "U1") (pin "95") (pinfunction "GND_95") (pintype "power_in"))
      (node (ref "U2") (pin "4") (pinfunction "GND_4") (pintype "power_in"))
      (node (ref "U3") (pin "4") (pinfunction "GND_4") (pintype "power_in"))
      (node (ref "Y1") (pin "2") (pinfunction "GND_2") (pintype "power_in"))
    )
    (net (code "59") (name "Net-(J1-Pad01)") (class "Default")
      (node (ref "J1") (pin "01") (pinfunction "01_01") (pintype "passive"))
      (node (ref "J1") (pin "02") (pinfunction "02_02") (pintype "passive"))
      (node (ref "R4") (pin "1") (pintype "passive"))
    )
    (net (code "60") (name "Net-(LED1-K)") (class "Default")
      (node (ref "LED1") (pin "2") (pinfunction "K_2") (pintype "passive"))
      (node (ref "R18") (pin "1") (pinfunction "1_1") (pintype "passive"))
    )
    (net (code "61") (name "Net-(U1A-PB9{slash}XIN)") (class "Default")
      (node (ref "R5") (pin "2") (pinfunction "2_2") (pintype "passive"))
      (node (ref "U1") (pin "142") (pinfunction "PB9/XIN_142") (pintype "bidirectional"))
    )
    (net (code "62") (name "Net-(U1B-JTAGSEL)") (class "Default")
      (node (ref "R3") (pin "2") (pinfunction "2_2") (pintype "passive"))
      (node (ref "U1") (pin "104") (pinfunction "JTAGSEL_104") (pintype "input"))
    )
    (net (code "63") (name "Net-(U1B-TST)") (class "Default")
      (node (ref "R2") (pin "2") (pinfunction "2_2") (pintype "passive"))
      (node (ref "U1") (pin "85") (pinfunction "TST_85") (pintype "input"))
    )
    (net (code "64") (name "Net-(Y1-OUT)") (class "Default")
      (node (ref "R5") (pin "1") (pinfunction "1_1") (pintype "passive"))
      (node (ref "Y1") (pin "3") (pinfunction "OUT_3") (pintype "output"))
    )
    (net (code "65") (name "VCC_1P2") (class "Default")
      (node (ref "C10") (pin "2") (pinfunction "2_2") (pintype "passive"))
      (node (ref "C11") (pin "2") (pinfunction "2_2") (pintype "passive"))
      (node (ref "C13") (pin "2") (pinfunction "2_2") (pintype "passive"))
      (node (ref "C14") (pin "2") (pinfunction "2_2") (pintype "passive"))
      (node (ref "C15") (pin "2") (pinfunction "2_2") (pintype "passive"))
      (node (ref "C16") (pin "2") (pinfunction "2_2") (pintype "passive"))
      (node (ref "C17") (pin "2") (pinfunction "2_2") (pintype "passive"))
      (node (ref "C18") (pin "2") (pinfunction "2_2") (pintype "passive"))
      (node (ref "C19") (pin "2") (pinfunction "2_2") (pintype "passive"))
      (node (ref "U1") (pin "107") (pinfunction "VDDCORE_107") (pintype "power_in"))
      (node (ref "U1") (pin "123") (pinfunction "VDDPLL_123") (pintype "power_in"))
      (node (ref "U1") (pin "139") (pinfunction "VDDUTMIC_139") (pintype "power_in"))
      (node (ref "U1") (pin "29") (pinfunction "VDDCORE_29") (pintype "power_in"))
      (node (ref "U1") (pin "3") (pinfunction "VDDOUT_3") (pintype "output"))
      (node (ref "U1") (pin "33") (pinfunction "VDDCORE_33") (pintype "power_in"))
      (node (ref "U1") (pin "50") (pinfunction "VDDCORE_50") (pintype "power_in"))
      (node (ref "U1") (pin "81") (pinfunction "VDDCORE_81") (pintype "power_in"))
    )
    (net (code "66") (name "VCC_3P3") (class "Default")
      (node (ref "C1") (pin "2") (pinfunction "2_2") (pintype "passive"))
      (node (ref "C12") (pin "2") (pinfunction "2_2") (pintype "passive"))
      (node (ref "C2") (pin "2") (pinfunction "2_2") (pintype "passive"))
      (node (ref "C20") (pin "1") (pinfunction "1_1") (pintype "passive"))
      (node (ref "C21") (pin "2") (pinfunction "2_2") (pintype "passive"))
      (node (ref "C22") (pin "1") (pinfunction "1_1") (pintype "passive"))
      (node (ref "C23") (pin "1") (pinfunction "1_1") (pintype "passive"))
      (node (ref "C3") (pin "2") (pinfunction "2_2") (pintype "passive"))
      (node (ref "C4") (pin "2") (pinfunction "2_2") (pintype "passive"))
      (node (ref "C5") (pin "2") (pinfunction "2_2") (pintype "passive"))
      (node (ref "C6") (pin "2") (pinfunction "2_2") (pintype "passive"))
      (node (ref "C7") (pin "2") (pinfunction "2_2") (pintype "passive"))
      (node (ref "C8") (pin "2") (pinfunction "2_2") (pintype "passive"))
      (node (ref "C9") (pin "2") (pinfunction "2_2") (pintype "passive"))
      (node (ref "LED1") (pin "1") (pinfunction "A_1") (pintype "passive"))
      (node (ref "R10") (pin "2") (pinfunction "2_2") (pintype "passive"))
      (node (ref "R11") (pin "2") (pinfunction "2_2") (pintype "passive"))
      (node (ref "R12") (pin "2") (pinfunction "2_2") (pintype "passive"))
      (node (ref "R13") (pin "2") (pinfunction "2_2") (pintype "passive"))
      (node (ref "R14") (pin "2") (pinfunction "2_2") (pintype "passive"))
      (node (ref "R15") (pin "2") (pinfunction "2_2") (pintype "passive"))
      (node (ref "R16") (pin "2") (pinfunction "2_2") (pintype "passive"))
      (node (ref "R17") (pin "2") (pinfunction "2_2") (pintype "passive"))
      (node (ref "R19") (pin "2") (pinfunction "2_2") (pintype "passive"))
      (node (ref "R4") (pin "2") (pintype "passive"))
      (node (ref "R6") (pin "2") (pinfunction "2_2") (pintype "passive"))
      (node (ref "R7") (pin "2") (pinfunction "2_2") (pintype "passive"))
      (node (ref "R8") (pin "2") (pinfunction "2_2") (pintype "passive"))
      (node (ref "R9") (pin "2") (pinfunction "2_2") (pintype "passive"))
      (node (ref "TP2") (pin "1") (pinfunction "1_1") (pintype "passive"))
      (node (ref "U1") (pin "134") (pinfunction "VDDUTMII_134") (pintype "power_in"))
      (node (ref "U1") (pin "143") (pinfunction "VDDPLLUSB_143") (pintype "power_in"))
      (node (ref "U1") (pin "30") (pinfunction "VDDIO_30") (pintype "power_in"))
      (node (ref "U1") (pin "43") (pinfunction "VDDIO_43") (pintype "power_in"))
      (node (ref "U1") (pin "5") (pinfunction "VDDIN_5") (pintype "power_in"))
      (node (ref "U1") (pin "72") (pinfunction "VDDIO_72") (pintype "power_in"))
      (node (ref "U1") (pin "80") (pinfunction "VDDIO_80") (pintype "power_in"))
      (node (ref "U1") (pin "9") (pinfunction "VREFP_9") (pintype "input"))
      (node (ref "U1") (pin "96") (pinfunction "VDDIO_96") (pintype "power_in"))
      (node (ref "U2") (pin "8") (pinfunction "VCC_8") (pintype "power_in"))
      (node (ref "U3") (pin "8") (pinfunction "VCC_8") (pintype "power_in"))
      (node (ref "Y1") (pin "4") (pinfunction "VCC_4") (pintype "power_in"))
    )
    (net (code "67") (name "unconnected-(U1A-PA0{slash}A17{slash}WKUP0{slash}TIOA0{slash}BA1{slash}I2SC0_MCK-Pad102)") (class "Default")
      (node (ref "U1") (pin "102") (pinfunction "PA0/A17/WKUP0/TIOA0/BA1/I2SC0_MCK_102") (pintype "bidirectional"))
    )
    (net (code "68") (name "unconnected-(U1A-PA7{slash}XIN32-Pad35)") (class "Default")
      (node (ref "U1") (pin "35") (pinfunction "PA7/XIN32_35") (pintype "bidirectional"))
    )
    (net (code "69") (name "unconnected-(U1A-PA8{slash}XIN32{slash}AFE0_ADTRG-Pad36)") (class "Default")
      (node (ref "U1") (pin "36") (pinfunction "PA8/XIN32/AFE0_ADTRG_36") (pintype "bidirectional"))
    )
    (net (code "70") (name "unconnected-(U1A-PA11{slash}QCS-Pad64)") (class "Default")
      (node (ref "U1") (pin "64") (pinfunction "PA11/QCS_64") (pintype "bidirectional"))
    )
    (net (code "71") (name "unconnected-(U1A-PA12{slash}QIO1-Pad68)") (class "Default")
      (node (ref "U1") (pin "68") (pinfunction "PA12/QIO1_68") (pintype "bidirectional"))
    )
    (net (code "72") (name "unconnected-(U1A-PA13{slash}QIO0-Pad42)") (class "Default")
      (node (ref "U1") (pin "42") (pinfunction "PA13/QIO0_42") (pintype "bidirectional"))
    )
    (net (code "73") (name "unconnected-(U1A-PA14{slash}QSCK-Pad51)") (class "Default")
      (node (ref "U1") (pin "51") (pinfunction "PA14/QSCK_51") (pintype "bidirectional"))
    )
    (net (code "74") (name "unconnected-(U1A-PA15{slash}D14{slash}TIOA1{slash}I2SC0_WS-Pad49)") (class "Default")
      (node (ref "U1") (pin "49") (pinfunction "PA15/D14/TIOA1/I2SC0_WS_49") (pintype "bidirectional"))
    )
    (net (code "75") (name "unconnected-(U1A-PA16{slash}D15{slash}TIOB1{slash}I2SC0_WI-Pad45)") (class "Default")
      (node (ref "U1") (pin "45") (pinfunction "PA16/D15/TIOB1/I2SC0_WI_45") (pintype "bidirectional"))
    )
    (net (code "76") (name "unconnected-(U1A-PA22{slash}PIODCCLK{slash}RK{slash}NCS2-Pad37)") (class "Default")
      (node (ref "U1") (pin "37") (pinfunction "PA22/PIODCCLK/RK/NCS2_37") (pintype "bidirectional"))
    )
    (net (code "77") (name "unconnected-(U1A-PA23{slash}A19{slash}SCK1-Pad46)") (class "Default")
      (node (ref "U1") (pin "46") (pinfunction "PA23/A19/SCK1_46") (pintype "bidirectional"))
    )
    (net (code "78") (name "unconnected-(U1A-PA24{slash}A20{slash}RTS1{slash}ISI_PCK-Pad56)") (class "Default")
      (node (ref "U1") (pin "56") (pinfunction "PA24/A20/RTS1/ISI_PCK_56") (pintype "bidirectional"))
    )
    (net (code "79") (name "unconnected-(U1A-PA25{slash}A23{slash}CTS1{slash}MCCK-Pad59)") (class "Default")
      (node (ref "U1") (pin "59") (pinfunction "PA25/A23/CTS1/MCCK_59") (pintype "bidirectional"))
    )
    (net (code "80") (name "unconnected-(U1A-PA26{slash}DCD1{slash}TIOA2{slash}MCDA2-Pad62)") (class "Default")
      (node (ref "U1") (pin "62") (pinfunction "PA26/DCD1/TIOA2/MCDA2_62") (pintype "bidirectional"))
    )
    (net (code "81") (name "unconnected-(U1A-PA27{slash}DTR1{slash}TIOB2{slash}MCDA3{slash}ISI_D7-Pad70)") (class "Default")
      (node (ref "U1") (pin "70") (pinfunction "PA27/DTR1/TIOB2/MCDA3/ISI_D7_70") (pintype "bidirectional"))
    )
    (net (code "82") (name "unconnected-(U1A-PA28{slash}DSR1{slash}TCLK1{slash}MCCDA-Pad112)") (class "Default")
      (node (ref "U1") (pin "112") (pinfunction "PA28/DSR1/TCLK1/MCCDA_112") (pintype "bidirectional"))
    )
    (net (code "83") (name "unconnected-(U1A-PA29{slash}RI1{slash}TCLK2-Pad129)") (class "Default")
      (node (ref "U1") (pin "129") (pinfunction "PA29/RI1/TCLK2_129") (pintype "bidirectional"))
    )
    (net (code "84") (name "unconnected-(U1A-PA30{slash}MCDA0{slash}I2SC0_DO-Pad116)") (class "Default")
      (node (ref "U1") (pin "116") (pinfunction "PA30/MCDA0/I2SC0_DO_116") (pintype "bidirectional"))
    )
    (net (code "85") (name "unconnected-(U1A-PA31{slash}SPI0_NPCS1{slash}PCK2{slash}MCDA1-Pad118)") (class "Default")
      (node (ref "U1") (pin "118") (pinfunction "PA31/SPI0_NPCS1/PCK2/MCDA1_118") (pintype "bidirectional"))
    )
    (net (code "86") (name "unconnected-(U1A-PB0{slash}AFE0_AD10{slash}RXD0{slash}TF-Pad21)") (class "Default")
      (node (ref "U1") (pin "21") (pinfunction "PB0/AFE0_AD10/RXD0/TF_21") (pintype "bidirectional"))
    )
    (net (code "87") (name "unconnected-(U1A-PB1{slash}AFE1_AD0{slash}TXD0{slash}TK{slash}GTSUCOMP-Pad20)") (class "Default")
      (node (ref "U1") (pin "20") (pinfunction "PB1/AFE1_AD0/TXD0/TK/GTSUCOMP_20") (pintype "bidirectional"))
    )
    (net (code "88") (name "unconnected-(U1A-PB4{slash}TDI{slash}TWD1{slash}MLBCLK{slash}TXD1-Pad105)") (class "Default")
      (node (ref "U1") (pin "105") (pinfunction "PB4/TDI/TWD1/MLBCLK/TXD1_105") (pintype "bidirectional"))
    )
    (net (code "89") (name "unconnected-(U1A-PB8{slash}XOUT-Pad141)") (class "Default")
      (node (ref "U1") (pin "141") (pinfunction "PB8/XOUT_141") (pintype "bidirectional+no_connect"))
    )
    (net (code "90") (name "unconnected-(U1A-PB12{slash}ERASE{slash}GTSUCOMP{slash}PCK0-Pad87)") (class "Default")
      (node (ref "U1") (pin "87") (pinfunction "PB12/ERASE/GTSUCOMP/PCK0_87") (pintype "bidirectional"))
    )
    (net (code "91") (name "unconnected-(U1A-PB13{slash}DAC0{slash}PCK0{slash}SCK0-Pad144)") (class "Default")
      (node (ref "U1") (pin "144") (pinfunction "PB13/DAC0/PCK0/SCK0_144") (pintype "bidirectional"))
    )
    (net (code "92") (name "unconnected-(U1A-PC16{slash}A21{slash}NAND_ALE-Pad100)") (class "Default")
      (node (ref "U1") (pin "100") (pinfunction "PC16/A21/NAND_ALE_100") (pintype "bidirectional"))
    )
    (net (code "93") (name "unconnected-(U1A-PC18{slash}A0{slash}NBS0-Pad111)") (class "Default")
      (node (ref "U1") (pin "111") (pinfunction "PC18/A0/NBS0_111") (pintype "bidirectional"))
    )
    (net (code "94") (name "unconnected-(U1A-PC19{slash}A1-Pad117)") (class "Default")
      (node (ref "U1") (pin "117") (pinfunction "PC19/A1_117") (pintype "bidirectional"))
    )
    (net (code "95") (name "unconnected-(U1A-PC20{slash}A2-Pad120)") (class "Default")
      (node (ref "U1") (pin "120") (pinfunction "PC20/A2_120") (pintype "bidirectional"))
    )
    (net (code "96") (name "unconnected-(U1A-PC21{slash}A3-Pad122)") (class "Default")
      (node (ref "U1") (pin "122") (pinfunction "PC21/A3_122") (pintype "bidirectional"))
    )
    (net (code "97") (name "unconnected-(U1A-PC22{slash}A4-Pad124)") (class "Default")
      (node (ref "U1") (pin "124") (pinfunction "PC22/A4_124") (pintype "bidirectional"))
    )
    (net (code "98") (name "unconnected-(U1A-PC23{slash}A5-Pad127)") (class "Default")
      (node (ref "U1") (pin "127") (pinfunction "PC23/A5_127") (pintype "bidirectional"))
    )
    (net (code "99") (name "unconnected-(U1A-PC24{slash}A6{slash}SPI1_SPCK-Pad130)") (class "Default")
      (node (ref "U1") (pin "130") (pinfunction "PC24/A6/SPI1_SPCK_130") (pintype "bidirectional"))
    )
    (net (code "100") (name "unconnected-(U1A-PC25{slash}A7{slash}SPI1_NPCS0-Pad133)") (class "Default")
      (node (ref "U1") (pin "133") (pinfunction "PC25/A7/SPI1_NPCS0_133") (pintype "bidirectional"))
    )
    (net (code "101") (name "unconnected-(U1A-PC26{slash}A8{slash}AFE1_AD7{slash}SPI1_MISO-Pad13)") (class "Default")
      (node (ref "U1") (pin "13") (pinfunction "PC26/A8/AFE1_AD7/SPI1_MISO_13") (pintype "bidirectional"))
    )
    (net (code "102") (name "unconnected-(U1A-PC27{slash}A9{slash}SPI1_MOSI-Pad12)") (class "Default")
      (node (ref "U1") (pin "12") (pinfunction "PC27/A9/SPI1_MOSI_12") (pintype "bidirectional"))
    )
    (net (code "103") (name "unconnected-(U1A-PC28{slash}A10{slash}TCLK4{slash}SPI1_NPCS1-Pad76)") (class "Default")
      (node (ref "U1") (pin "76") (pinfunction "PC28/A10/TCLK4/SPI1_NPCS1_76") (pintype "bidirectional"))
    )
    (net (code "104") (name "unconnected-(U1A-PC29{slash}A11{slash}AFE1_AD4{slash}TIOA5{slash}SPI1_NPCS2-Pad16)") (class "Default")
      (node (ref "U1") (pin "16") (pinfunction "PC29/A11/AFE1_AD4/TIOA5/SPI1_NPCS2_16") (pintype "bidirectional"))
    )
    (net (code "105") (name "unconnected-(U1A-PC30{slash}A12{slash}AFE1_AD5{slash}TIOB5{slash}SPI1_NPCS3-Pad15)") (class "Default")
      (node (ref "U1") (pin "15") (pinfunction "PC30/A12/AFE1_AD5/TIOB5/SPI1_NPCS3_15") (pintype "bidirectional"))
    )
    (net (code "106") (name "unconnected-(U1A-PC31{slash}A13{slash}AFE1_AD6{slash}TCLK5-Pad14)") (class "Default")
      (node (ref "U1") (pin "14") (pinfunction "PC31/A13/AFE1_AD6/TCLK5_14") (pintype "bidirectional"))
    )
    (net (code "107") (name "unconnected-(U1A-PD6{slash}GRX1{slash}TRACED2{slash}DSR2-Pad121)") (class "Default")
      (node (ref "U1") (pin "121") (pinfunction "PD6/GRX1/TRACED2/DSR2_121") (pintype "bidirectional"))
    )
    (net (code "108") (name "unconnected-(U1A-PD7{slash}GRXER{slash}TRACED3{slash}RI2-Pad119)") (class "Default")
      (node (ref "U1") (pin "119") (pinfunction "PD7/GRXER/TRACED3/RI2_119") (pintype "bidirectional"))
    )
    (net (code "109") (name "unconnected-(U1A-PD8{slash}GMDC{slash}TRACECLK-Pad113)") (class "Default")
      (node (ref "U1") (pin "113") (pinfunction "PD8/GMDC/TRACECLK_113") (pintype "bidirectional"))
    )
    (net (code "110") (name "unconnected-(U1A-PD9{slash}GMDIO{slash}AFE1_ADTRG-Pad110)") (class "Default")
      (node (ref "U1") (pin "110") (pinfunction "PD9/GMDIO/AFE1_ADTRG_110") (pintype "bidirectional"))
    )
    (net (code "111") (name "unconnected-(U1A-PD10{slash}GCRS{slash}TD{slash}MLBSIG-Pad101)") (class "Default")
      (node (ref "U1") (pin "101") (pinfunction "PD10/GCRS/TD/MLBSIG_101") (pintype "bidirectional"))
    )
    (net (code "112") (name "unconnected-(U1A-PD11{slash}GRX2{slash}GTSUCOMP{slash}ISI_D5-Pad98)") (class "Default")
      (node (ref "U1") (pin "98") (pinfunction "PD11/GRX2/GTSUCOMP/ISI_D5_98") (pintype "bidirectional"))
    )
    (net (code "113") (name "unconnected-(U1A-PD12{slash}GRX3{slash}CANTX1{slash}SPI0_NPCS2{slash}ISI_D6-Pad92)") (class "Default")
      (node (ref "U1") (pin "92") (pinfunction "PD12/GRX3/CANTX1/SPI0_NPCS2/ISI_D6_92") (pintype "bidirectional"))
    )
    (net (code "114") (name "unconnected-(U1A-PD13{slash}GCOL{slash}SDA10-Pad88)") (class "Default")
      (node (ref "U1") (pin "88") (pinfunction "PD13/GCOL/SDA10_88") (pintype "bidirectional"))
    )
    (net (code "115") (name "unconnected-(U1A-PD14{slash}GRXCK{slash}SDCKE-Pad84)") (class "Default")
      (node (ref "U1") (pin "84") (pinfunction "PD14/GRXCK/SDCKE_84") (pintype "bidirectional"))
    )
    (net (code "116") (name "unconnected-(U1A-PD15{slash}GTX2{slash}RXD2{slash}NWR1_NBS1-Pad106)") (class "Default")
      (node (ref "U1") (pin "106") (pinfunction "PD15/GTX2/RXD2/NWR1_NBS1_106") (pintype "bidirectional"))
    )
    (net (code "117") (name "unconnected-(U1A-PD16{slash}GTX3{slash}TXD2{slash}RAS-Pad78)") (class "Default")
      (node (ref "U1") (pin "78") (pinfunction "PD16/GTX3/TXD2/RAS_78") (pintype "bidirectional"))
    )
    (net (code "118") (name "unconnected-(U1A-PD17{slash}GTXER{slash}SCK2{slash}CAS-Pad74)") (class "Default")
      (node (ref "U1") (pin "74") (pinfunction "PD17/GTXER/SCK2/CAS_74") (pintype "bidirectional"))
    )
    (net (code "119") (name "unconnected-(U1A-PD18{slash}NCS1_SDCS{slash}RTS2{slash}URXD4-Pad69)") (class "Default")
      (node (ref "U1") (pin "69") (pinfunction "PD18/NCS1_SDCS/RTS2/URXD4_69") (pintype "bidirectional"))
    )
    (net (code "120") (name "unconnected-(U1A-PD19{slash}NCS3{slash}CTS2{slash}UTXD4-Pad67)") (class "Default")
      (node (ref "U1") (pin "67") (pinfunction "PD19/NCS3/CTS2/UTXD4_67") (pintype "bidirectional"))
    )
    (net (code "121") (name "unconnected-(U1A-PD20{slash}SPI0_MISO{slash}GTSUCOMP-Pad65)") (class "Default")
      (node (ref "U1") (pin "65") (pinfunction "PD20/SPI0_MISO/GTSUCOMP_65") (pintype "bidirectional"))
    )
    (net (code "122") (name "unconnected-(U1A-PD21{slash}SPI0_MOSI{slash}TIOA11{slash}ISI_D1-Pad63)") (class "Default")
      (node (ref "U1") (pin "63") (pinfunction "PD21/SPI0_MOSI/TIOA11/ISI_D1_63") (pintype "bidirectional"))
    )
    (net (code "123") (name "unconnected-(U1A-PD22{slash}SPI0_SPCK{slash}TIOB11{slash}ISI_D0-Pad60)") (class "Default")
      (node (ref "U1") (pin "60") (pinfunction "PD22/SPI0_SPCK/TIOB11/ISI_D0_60") (pintype "bidirectional"))
    )
    (net (code "124") (name "unconnected-(U1A-PD29{slash}SDWE-Pad108)") (class "Default")
      (node (ref "U1") (pin "108") (pinfunction "PD29/SDWE_108") (pintype "bidirectional"))
    )
    (net (code "125") (name "unconnected-(U1A-PD31{slash}QIO3{slash}UTXD3{slash}PCK2{slash}ISI_D11-Pad2)") (class "Default")
      (node (ref "U1") (pin "2") (pinfunction "PD31/QIO3/UTXD3/PCK2/ISI_D11_2") (pintype "bidirectional"))
    )
    (net (code "126") (name "unconnected-(U1A-PE0{slash}D8{slash}AFE1_AD11{slash}TIOA9{slash}I2SC1_WS-Pad4)") (class "Default")
      (node (ref "U1") (pin "4") (pinfunction "PE0/D8/AFE1_AD11/TIOA9/I2SC1_WS_4") (pintype "bidirectional"))
    )
    (net (code "127") (name "unconnected-(U1A-PE1{slash}D9{slash}TIOB9{slash}I2SC1_DO-Pad6)") (class "Default")
      (node (ref "U1") (pin "6") (pinfunction "PE1/D9/TIOB9/I2SC1_DO_6") (pintype "bidirectional"))
    )
    (net (code "128") (name "unconnected-(U1A-PE2{slash}D10{slash}TCLK9{slash}I2SC1_DI-Pad7)") (class "Default")
      (node (ref "U1") (pin "7") (pinfunction "PE2/D10/TCLK9/I2SC1_DI_7") (pintype "bidirectional"))
    )
    (net (code "129") (name "unconnected-(U1A-PE3{slash}D11{slash}AFE1_AD10{slash}TIOA10-Pad10)") (class "Default")
      (node (ref "U1") (pin "10") (pinfunction "PE3/D11/AFE1_AD10/TIOA10_10") (pintype "bidirectional"))
    )
    (net (code "130") (name "unconnected-(U1B-HSDM-Pad136)") (class "Default")
      (node (ref "U1") (pin "136") (pinfunction "HSDM_136") (pintype "bidirectional+no_connect"))
    )
    (net (code "131") (name "unconnected-(U1B-HSDP-Pad137)") (class "Default")
      (node (ref "U1") (pin "137") (pinfunction "HSDP_137") (pintype "bidirectional+no_connect"))
    )
    (net (code "132") (name "unconnected-(U1B-VBG-Pad140)") (class "Default")
      (node (ref "U1") (pin "140") (pinfunction "VBG_140") (pintype "input+no_connect"))
    )
    (net (code "133") (name "unconnected-(Y1-EN{slash}NC-Pad1)") (class "Default")
      (node (ref "Y1") (pin "1") (pinfunction "EN/NC_1") (pintype "input+no_connect"))
    )
  )
)
